# dasblinkenhat-controller-mk-1_1.net
KiCad netlist of a schematic drawn in EAGLE
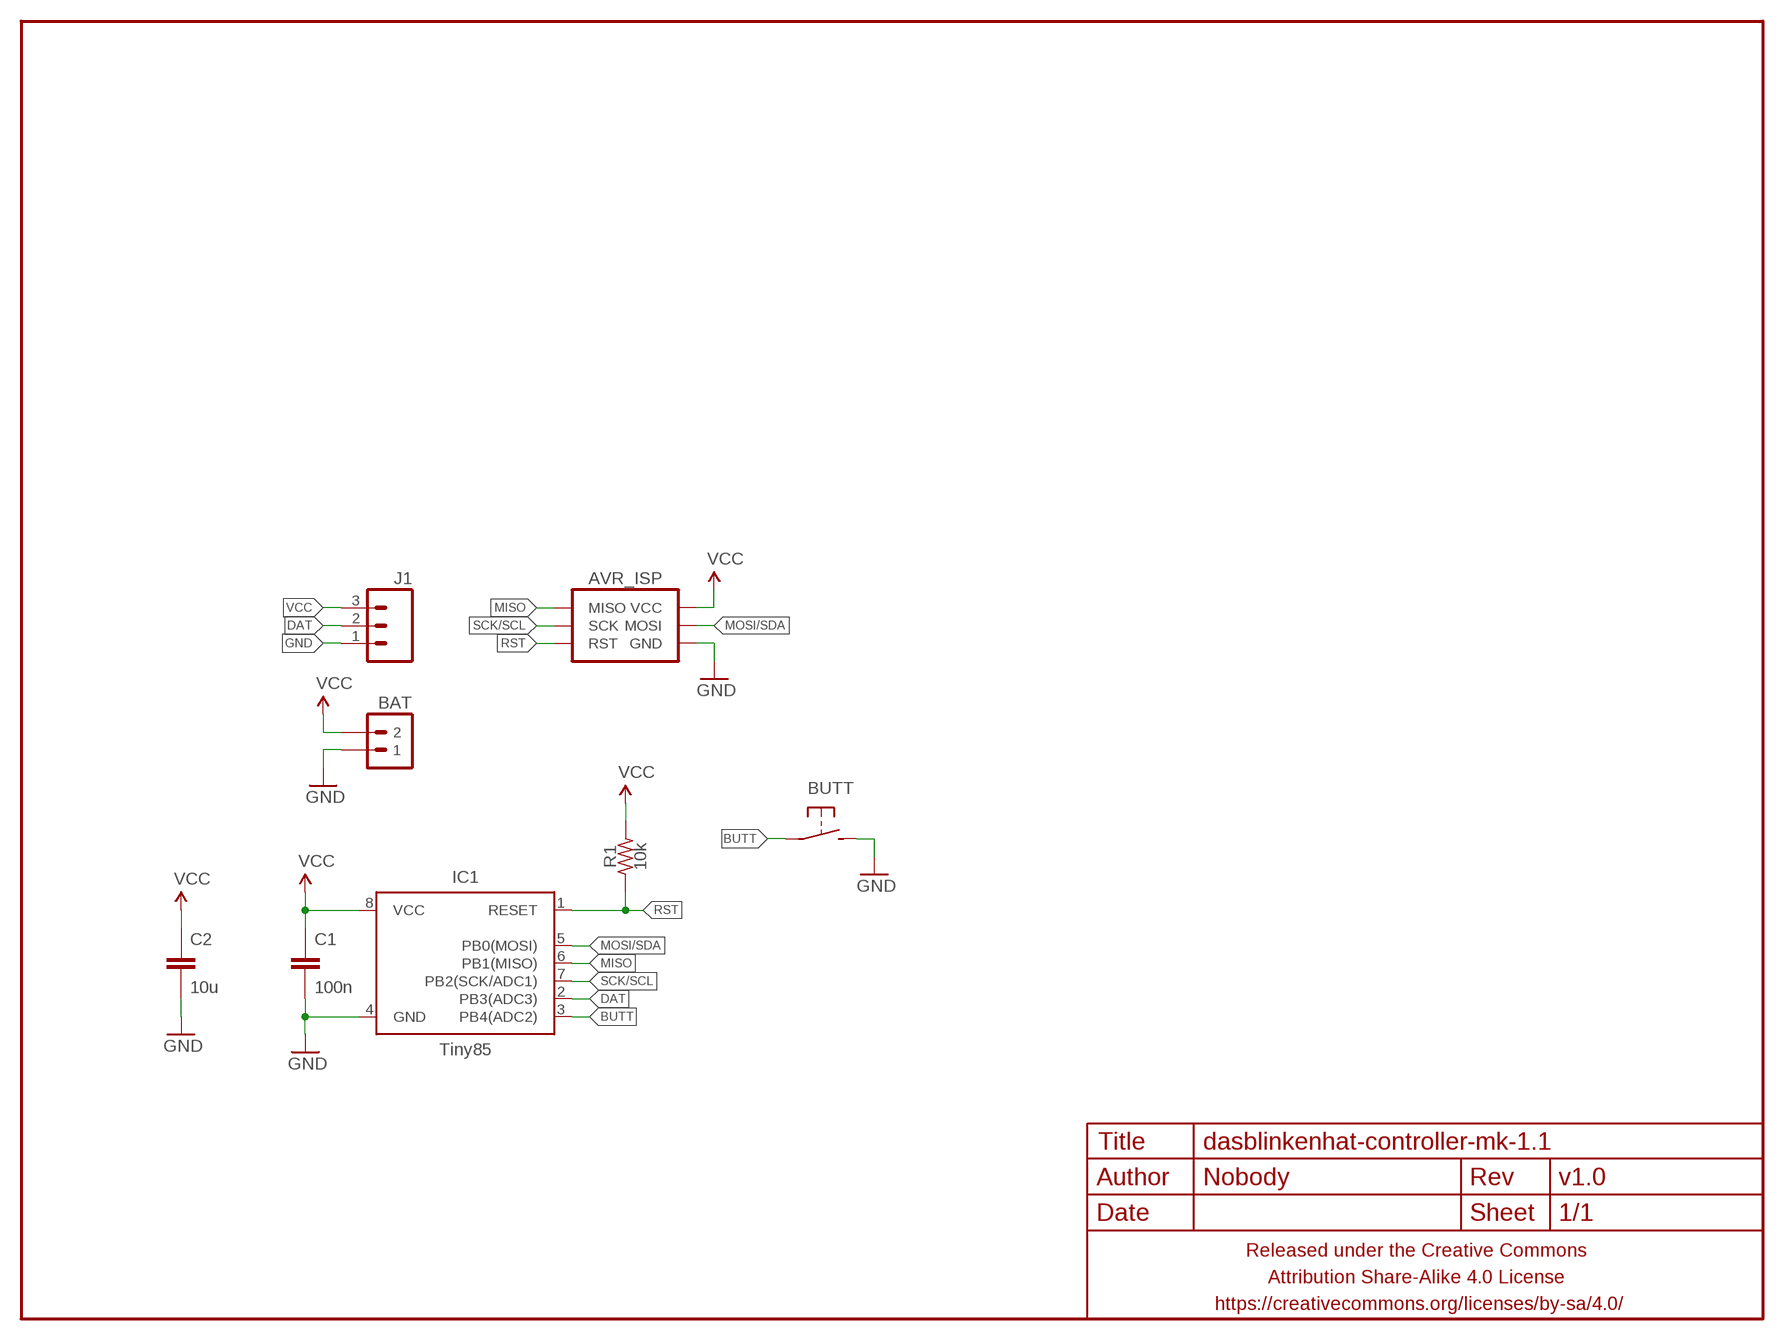
[diagram p0: schematic, sheet 1]

(export (version "E")
  (design (tool "Eeschema 10.0.6"))
  (components
    (comp (ref "AVR_ISP")
      (value "AVR_SPI_PRG_6TESTPOINTS")
      (footprint "eagle-import:2X3_TEST_POINTS")
      (libsource (lib "eagle-import") (part "AVR_SPI_PRG_6TESTPOINTS"))
    )
    (comp (ref "BAT")
      (value "M02JST-2MM-SMT")
      (footprint "eagle-import:JST-2-SMD")
      (libsource (lib "eagle-import") (part "M02JST-2MM-SMT"))
    )
    (comp (ref "BUTT")
      (value "DTS-6MM")
      (footprint "eagle-import:TACTILE-SWITCH-SMD")
      (libsource (lib "eagle-import") (part "SPST-NO-TACTSMD-TINY"))
    )
    (comp (ref "C1")
      (value "100n")
      (footprint "eagle-import:C0603")
      (libsource (lib "eagle-import") (part "CAPACITOR-CERAMICC0603"))
    )
    (comp (ref "C2")
      (value "10u")
      (footprint "eagle-import:C0805")
      (libsource (lib "eagle-import") (part "CAPACITOR-CERAMICC0805"))
    )
    (comp (ref "FRAME1")
      (value "FRAME-LETTERNO_PACKAGE")
      (footprint "eagle-import:DUMMY")
      (fields (field (name "VERSION") "v1.0") (field (name "DESIGNER") "Nobody"))
      (libsource (lib "eagle-import") (part "FRAME-LETTERNO_PACKAGE"))
    )
    (comp (ref "IC1")
      (value "Tiny85")
      (footprint "eagle-import:SO08-EIAJ")
      (libsource (lib "eagle-import") (part "ATTINY45TINY85-20-SOICW"))
    )
    (comp (ref "J1")
      (value "M03JST-XH-RA-PTH")
      (footprint "eagle-import:JST-3-XH-RA-PTH")
      (libsource (lib "eagle-import") (part "M03JST-XH-RA-PTH"))
    )
    (comp (ref "R1")
      (value "10k")
      (footprint "eagle-import:R0603")
      (libsource (lib "eagle-import") (part "RESISTORR0603"))
    )
  )
  (nets
    (net (code "1") (name "BUTT") (class "Default")
      (node (ref "BUTT") (pin "A@1") (pinfunction "1_A@1") (pintype "passive"))
      (node (ref "BUTT") (pin "A@2") (pinfunction "1_A@2") (pintype "passive"))
      (node (ref "IC1") (pin "3") (pinfunction "PB4(ADC2)_3") (pintype "bidirectional"))
    )
    (net (code "2") (name "DAT") (class "Default")
      (node (ref "IC1") (pin "2") (pinfunction "PB3(ADC3)_2") (pintype "bidirectional"))
      (node (ref "J1") (pin "2") (pinfunction "2_2") (pintype "passive"))
    )
    (net (code "3") (name "GND") (class "Default")
      (node (ref "AVR_ISP") (pin "6") (pinfunction "GND_6") (pintype "passive"))
      (node (ref "BAT") (pin "2") (pinfunction "1_2") (pintype "passive"))
      (node (ref "BUTT") (pin "B@1") (pinfunction "2_B@1") (pintype "passive"))
      (node (ref "BUTT") (pin "B@2") (pinfunction "2_B@2") (pintype "passive"))
      (node (ref "C1") (pin "2") (pinfunction "2_2") (pintype "passive"))
      (node (ref "C2") (pin "2") (pinfunction "2_2") (pintype "passive"))
      (node (ref "IC1") (pin "4") (pinfunction "GND_4") (pintype "bidirectional"))
      (node (ref "J1") (pin "1") (pinfunction "1_1") (pintype "passive"))
    )
    (net (code "4") (name "MISO") (class "Default")
      (node (ref "AVR_ISP") (pin "1") (pinfunction "MISO_1") (pintype "passive"))
      (node (ref "IC1") (pin "6") (pinfunction "PB1(MISO)_6") (pintype "bidirectional"))
    )
    (net (code "5") (name "MOSI{slash}SDA") (class "Default")
      (node (ref "AVR_ISP") (pin "4") (pinfunction "MOSI_4") (pintype "passive"))
      (node (ref "IC1") (pin "5") (pinfunction "PB0(MOSI)_5") (pintype "bidirectional"))
    )
    (net (code "6") (name "RST") (class "Default")
      (node (ref "AVR_ISP") (pin "5") (pinfunction "RST_5") (pintype "passive"))
      (node (ref "IC1") (pin "1") (pinfunction "RESET_1") (pintype "bidirectional"))
      (node (ref "R1") (pin "1") (pinfunction "1_1") (pintype "passive"))
    )
    (net (code "7") (name "SCK{slash}SCL") (class "Default")
      (node (ref "AVR_ISP") (pin "3") (pinfunction "SCK_3") (pintype "passive"))
      (node (ref "IC1") (pin "7") (pinfunction "PB2(SCK/ADC1)_7") (pintype "bidirectional"))
    )
    (net (code "8") (name "VCC") (class "Default")
      (node (ref "AVR_ISP") (pin "2") (pinfunction "VCC_2") (pintype "passive"))
      (node (ref "BAT") (pin "1") (pinfunction "2_1") (pintype "passive"))
      (node (ref "C1") (pin "1") (pinfunction "1_1") (pintype "passive"))
      (node (ref "C2") (pin "1") (pinfunction "1_1") (pintype "passive"))
      (node (ref "IC1") (pin "8") (pinfunction "VCC_8") (pintype "bidirectional"))
      (node (ref "J1") (pin "3") (pinfunction "3_3") (pintype "passive"))
      (node (ref "R1") (pin "2") (pinfunction "2_2") (pintype "passive"))
    )
  )
)
